# SD_Card.net
KiCad netlist of a schematic drawn in Altium Designer
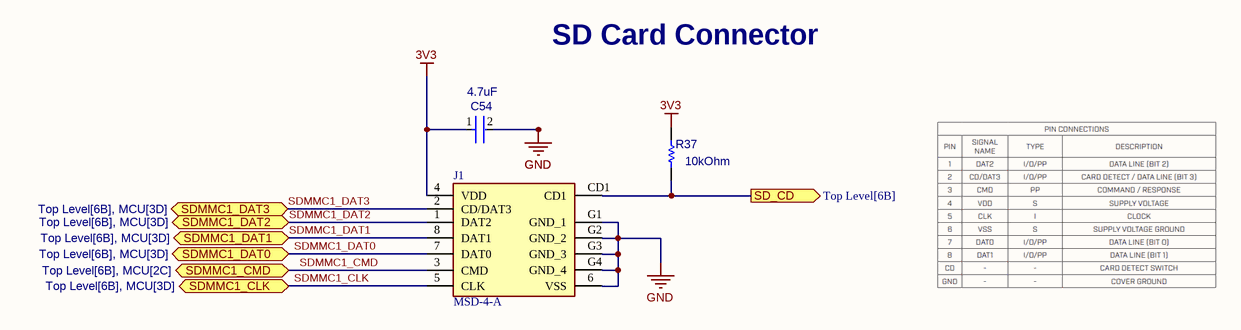
[diagram p0: SD Card.SchDoc]

(export (version "E")
  (design (tool "Eeschema 10.0.6"))
  (components
    (comp (ref "C54")
      (value "CC0603KRX7R9BB103")
      (footprint "FP-CC0603-DA-MFG")
      (description "CAP CER 10000PF 50V X7R 0603")
      (fields (field (name "TOLERANCE") "0.1") (field (name "MANUFACTURER") "YAGEO"))
      (libsource (lib "Altium Content Vault") (part "11868f565c42a9108669ba33697ecf6"))
    )
    (comp (ref "J1")
      (value "MSD-4-A")
      (footprint "MSD4A")
      (description "Connector")
      (fields (field (name "MOUSER PART NUMBER") "179-MSD-4-A"))
      (libsource (lib "C2S") (part "MSD-4-A"))
    )
    (comp (ref "R37")
      (value "RC0603JR-070RL")
      (footprint "RESC1608X55X25ML10T15")
      (description "Chip Resistor, 0 Ohm, +/- 5%, 0.1 W, -55 to 155 degC, 0603 (1608 Metric), RoHS, Tape and Reel")
      (fields (field (name "TOLERANCE") "5%") (field (name "MANUFACTURER") "Yageo"))
      (libsource (lib "Altium Content Vault") (part "RES-2"))
    )
  )
  (nets
    (net (code "1") (name "/SDMMC1_CLK") (class "Default")
      (node (ref "J1") (pin "5") (pinfunction "CLK_5") (pintype "passive"))
    )
    (net (code "2") (name "/SDMMC1_CMD") (class "Default")
      (node (ref "J1") (pin "3") (pinfunction "CMD_3") (pintype "passive"))
    )
    (net (code "3") (name "/SDMMC1_DAT0") (class "Default")
      (node (ref "J1") (pin "7") (pinfunction "DAT0_7") (pintype "passive"))
    )
    (net (code "4") (name "/SDMMC1_DAT1") (class "Default")
      (node (ref "J1") (pin "8") (pinfunction "DAT1_8") (pintype "passive"))
    )
    (net (code "5") (name "/SDMMC1_DAT2") (class "Default")
      (node (ref "J1") (pin "1") (pinfunction "DAT2_1") (pintype "passive"))
    )
    (net (code "6") (name "/SDMMC1_DAT3") (class "Default")
      (node (ref "J1") (pin "2") (pinfunction "CD/DAT3_2") (pintype "passive"))
    )
    (net (code "7") (name "/SD_CD") (class "Default")
      (node (ref "J1") (pin "CD1") (pinfunction "CD1_CD1") (pintype "passive"))
      (node (ref "R37") (pin "2") (pinfunction "2_2") (pintype "passive"))
    )
    (net (code "8") (name "3V3") (class "Default")
      (node (ref "C54") (pin "1") (pinfunction "1_1") (pintype "passive"))
      (node (ref "J1") (pin "4") (pinfunction "VDD_4") (pintype "passive"))
      (node (ref "R37") (pin "1") (pinfunction "1_1") (pintype "passive"))
    )
    (net (code "9") (name "GND") (class "Default")
      (node (ref "C54") (pin "2") (pinfunction "2_2") (pintype "passive"))
      (node (ref "J1") (pin "6") (pinfunction "VSS_6") (pintype "passive"))
      (node (ref "J1") (pin "G1") (pinfunction "GND_1_G1") (pintype "passive"))
      (node (ref "J1") (pin "G2") (pinfunction "GND_2_G2") (pintype "passive"))
      (node (ref "J1") (pin "G3") (pinfunction "GND_3_G3") (pintype "passive"))
      (node (ref "J1") (pin "G4") (pinfunction "GND_4_G4") (pintype "passive"))
    )
  )
)
